# Lights.net
KiCad netlist of a schematic drawn in Altium Designer
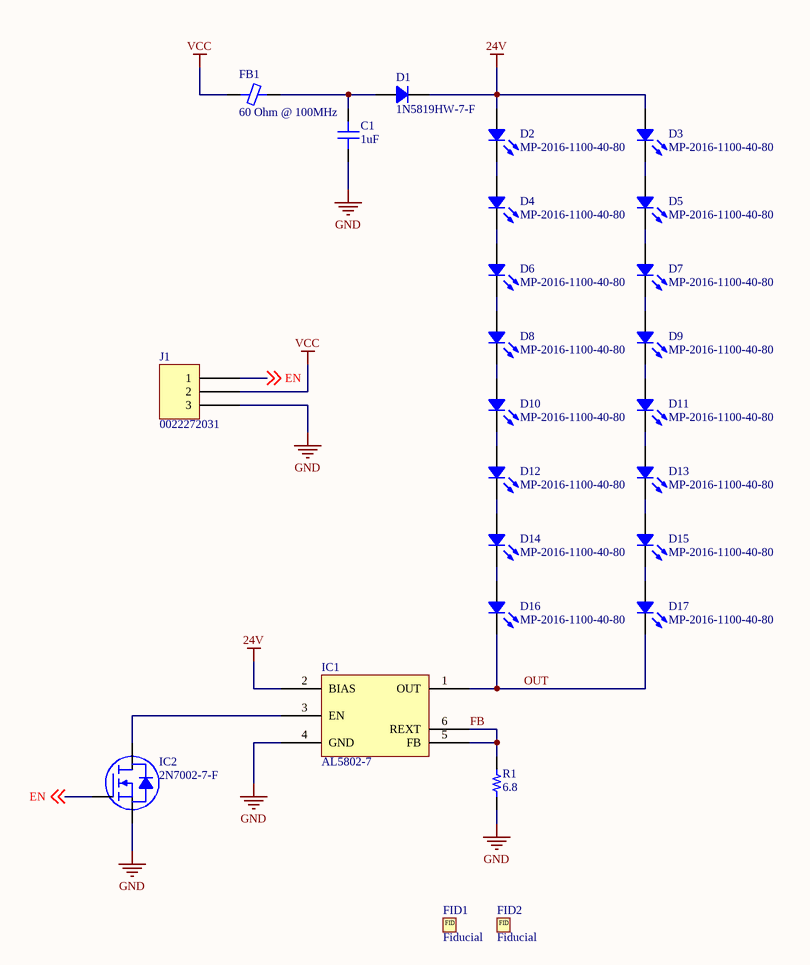
[diagram p0: Lights.SchDoc]

(export (version "E")
  (design (tool "Eeschema 10.0.6"))
  (components
    (comp (ref "C1")
      (value "1uF")
      (footprint "CAP 0603/1608")
      (description "CAP CER 1UF 50V X7R 0603")
      (fields (field (name "PART NUMBER") "UMK107AB7105KA-T") (field (name "MANUFACTURER") "Taiyo Yuden"))
      (libsource (lib "Celestial Library Database") (part "Capacitor"))
    )
    (comp (ref "D1")
      (value "1N5819HW-7-F")
      (footprint "SOD-123")
      (description "DIODE SCHOTTKY 40V 1A SOD123")
      (fields (field (name "MANUFACTURER") "Diodes Incorporated"))
      (libsource (lib "Celestial Library Database") (part "Diode"))
    )
    (comp (ref "D2")
      (value "MP-2016-1100-40-80")
      (footprint "LUMINUS MP-2016")
      (description "LED XNOVA NEUTRAL WHT 4000K 0806")
      (fields (field (name "MANUFACTURER") "Luminus Devices Inc."))
      (libsource (lib "Celestial Library Database") (part "LED"))
    )
    (comp (ref "D3")
      (value "MP-2016-1100-40-80")
      (footprint "LUMINUS MP-2016")
      (description "LED XNOVA NEUTRAL WHT 4000K 0806")
      (fields (field (name "MANUFACTURER") "Luminus Devices Inc."))
      (libsource (lib "Celestial Library Database") (part "LED"))
    )
    (comp (ref "D4")
      (value "MP-2016-1100-40-80")
      (footprint "LUMINUS MP-2016")
      (description "LED XNOVA NEUTRAL WHT 4000K 0806")
      (fields (field (name "MANUFACTURER") "Luminus Devices Inc."))
      (libsource (lib "Celestial Library Database") (part "LED"))
    )
    (comp (ref "D5")
      (value "MP-2016-1100-40-80")
      (footprint "LUMINUS MP-2016")
      (description "LED XNOVA NEUTRAL WHT 4000K 0806")
      (fields (field (name "MANUFACTURER") "Luminus Devices Inc."))
      (libsource (lib "Celestial Library Database") (part "LED"))
    )
    (comp (ref "D6")
      (value "MP-2016-1100-40-80")
      (footprint "LUMINUS MP-2016")
      (description "LED XNOVA NEUTRAL WHT 4000K 0806")
      (fields (field (name "MANUFACTURER") "Luminus Devices Inc."))
      (libsource (lib "Celestial Library Database") (part "LED"))
    )
    (comp (ref "D7")
      (value "MP-2016-1100-40-80")
      (footprint "LUMINUS MP-2016")
      (description "LED XNOVA NEUTRAL WHT 4000K 0806")
      (fields (field (name "MANUFACTURER") "Luminus Devices Inc."))
      (libsource (lib "Celestial Library Database") (part "LED"))
    )
    (comp (ref "D8")
      (value "MP-2016-1100-40-80")
      (footprint "LUMINUS MP-2016")
      (description "LED XNOVA NEUTRAL WHT 4000K 0806")
      (fields (field (name "MANUFACTURER") "Luminus Devices Inc."))
      (libsource (lib "Celestial Library Database") (part "LED"))
    )
    (comp (ref "D9")
      (value "MP-2016-1100-40-80")
      (footprint "LUMINUS MP-2016")
      (description "LED XNOVA NEUTRAL WHT 4000K 0806")
      (fields (field (name "MANUFACTURER") "Luminus Devices Inc."))
      (libsource (lib "Celestial Library Database") (part "LED"))
    )
    (comp (ref "D10")
      (value "MP-2016-1100-40-80")
      (footprint "LUMINUS MP-2016")
      (description "LED XNOVA NEUTRAL WHT 4000K 0806")
      (fields (field (name "MANUFACTURER") "Luminus Devices Inc."))
      (libsource (lib "Celestial Library Database") (part "LED"))
    )
    (comp (ref "D11")
      (value "MP-2016-1100-40-80")
      (footprint "LUMINUS MP-2016")
      (description "LED XNOVA NEUTRAL WHT 4000K 0806")
      (fields (field (name "MANUFACTURER") "Luminus Devices Inc."))
      (libsource (lib "Celestial Library Database") (part "LED"))
    )
    (comp (ref "D12")
      (value "MP-2016-1100-40-80")
      (footprint "LUMINUS MP-2016")
      (description "LED XNOVA NEUTRAL WHT 4000K 0806")
      (fields (field (name "MANUFACTURER") "Luminus Devices Inc."))
      (libsource (lib "Celestial Library Database") (part "LED"))
    )
    (comp (ref "D13")
      (value "MP-2016-1100-40-80")
      (footprint "LUMINUS MP-2016")
      (description "LED XNOVA NEUTRAL WHT 4000K 0806")
      (fields (field (name "MANUFACTURER") "Luminus Devices Inc."))
      (libsource (lib "Celestial Library Database") (part "LED"))
    )
    (comp (ref "D14")
      (value "MP-2016-1100-40-80")
      (footprint "LUMINUS MP-2016")
      (description "LED XNOVA NEUTRAL WHT 4000K 0806")
      (fields (field (name "MANUFACTURER") "Luminus Devices Inc."))
      (libsource (lib "Celestial Library Database") (part "LED"))
    )
    (comp (ref "D15")
      (value "MP-2016-1100-40-80")
      (footprint "LUMINUS MP-2016")
      (description "LED XNOVA NEUTRAL WHT 4000K 0806")
      (fields (field (name "MANUFACTURER") "Luminus Devices Inc."))
      (libsource (lib "Celestial Library Database") (part "LED"))
    )
    (comp (ref "D16")
      (value "MP-2016-1100-40-80")
      (footprint "LUMINUS MP-2016")
      (description "LED XNOVA NEUTRAL WHT 4000K 0806")
      (fields (field (name "MANUFACTURER") "Luminus Devices Inc."))
      (libsource (lib "Celestial Library Database") (part "LED"))
    )
    (comp (ref "D17")
      (value "MP-2016-1100-40-80")
      (footprint "LUMINUS MP-2016")
      (description "LED XNOVA NEUTRAL WHT 4000K 0806")
      (fields (field (name "MANUFACTURER") "Luminus Devices Inc."))
      (libsource (lib "Celestial Library Database") (part "LED"))
    )
    (comp (ref "FB1")
      (value "60 Ohm @ 100MHz")
      (footprint "FER 0603/1608")
      (description "FERRITE CHIP 60 OHM 2000MA 0603")
      (fields
        (field (name "PART NUMBER") "CIC10J600NC")
        (field (name "MANUFACTURER") "Samsung Electro-Mechanics America, Inc.")
      )
      (libsource (lib "Celestial Library Database") (part "Ferrite Chip"))
    )
    (comp (ref "FID1")
      (value "Fiducial")
      (footprint "1MM FID")
      (libsource (lib "Fiducial") (part "Fiducial"))
    )
    (comp (ref "FID2")
      (value "Fiducial")
      (footprint "1MM FID")
      (libsource (lib "Fiducial") (part "Fiducial"))
    )
    (comp (ref "IC1")
      (value "AL5802-7")
      (footprint "DIODES SOT-23-6 W6")
      (description "IC LED DRVR LIN DIM 120MA SOT26")
      (fields (field (name "MANUFACTURER") "Diodes Incorporated"))
      (libsource (lib "Celestial Library Database") (part "DIODES INC AL5802"))
    )
    (comp (ref "IC2")
      (value "2N7002-7-F")
      (footprint "DIODES SOT-23-3")
      (description "MOSFET N-CH 60V 115MA SOT23-3")
      (fields (field (name "MANUFACTURER") "Diodes Incorporated"))
      (libsource (lib "Celestial Library Database") (part "DIODES INC MOSFET N-CH SOT-23-3"))
    )
    (comp (ref "J1")
      (value "0022272031")
      (footprint "MOLEX KK 0022272031")
      (description "CONN HEADER 3POS .100 VERT TIN")
      (fields (field (name "MANUFACTURER") "Molex, LLC"))
      (libsource (lib "Celestial Library Database") (part "3 Pin"))
    )
    (comp (ref "R1")
      (value "6.8")
      (footprint "RES 0805/2012")
      (description "RES SMD 6.8 OHM 1% 1/8W 0805")
      (fields
        (field (name "PART NUMBER") "ERJ-6RQF6R8V")
        (field (name "MANUFACTURER") "Panasonic Electronic Components")
      )
      (libsource (lib "Celestial Library Database") (part "Resistor"))
    )
  )
  (nets
    (net (code "1") (name "/FB") (class "Default")
      (node (ref "IC1") (pin "5") (pinfunction "FB_5") (pintype "passive"))
      (node (ref "IC1") (pin "6") (pinfunction "REXT_6") (pintype "passive"))
      (node (ref "R1") (pin "2") (pinfunction "2_2") (pintype "passive"))
    )
    (net (code "2") (name "/OUT") (class "Default")
      (node (ref "D16") (pin "2") (pinfunction "2_2") (pintype "passive"))
      (node (ref "D17") (pin "2") (pinfunction "2_2") (pintype "passive"))
      (node (ref "IC1") (pin "1") (pinfunction "OUT_1") (pintype "passive"))
    )
    (net (code "3") (name "24V") (class "Default")
      (node (ref "D1") (pin "2") (pinfunction "2_2") (pintype "passive"))
      (node (ref "D2") (pin "1") (pinfunction "1_1") (pintype "passive"))
      (node (ref "D3") (pin "1") (pinfunction "1_1") (pintype "passive"))
      (node (ref "IC1") (pin "2") (pinfunction "BIAS_2") (pintype "passive"))
    )
    (net (code "4") (name "EN") (class "Default")
      (node (ref "IC2") (pin "1") (pinfunction "G_1") (pintype "passive"))
      (node (ref "J1") (pin "1") (pinfunction "1_1") (pintype "passive"))
    )
    (net (code "5") (name "GND") (class "Default")
      (node (ref "C1") (pin "1") (pinfunction "1_1") (pintype "passive"))
      (node (ref "IC1") (pin "4") (pinfunction "GND_4") (pintype "passive"))
      (node (ref "IC2") (pin "3") (pinfunction "S_3") (pintype "passive"))
      (node (ref "J1") (pin "3") (pinfunction "3_3") (pintype "passive"))
      (node (ref "R1") (pin "1") (pinfunction "1_1") (pintype "passive"))
    )
    (net (code "6") (name "Net-(C1-Pad2)") (class "Default")
      (node (ref "C1") (pin "2") (pinfunction "2_2") (pintype "passive"))
      (node (ref "D1") (pin "1") (pinfunction "1_1") (pintype "passive"))
      (node (ref "FB1") (pin "2") (pinfunction "2_2") (pintype "passive"))
    )
    (net (code "7") (name "Net-(D2-Pad2)") (class "Default")
      (node (ref "D2") (pin "2") (pinfunction "2_2") (pintype "passive"))
      (node (ref "D4") (pin "1") (pinfunction "1_1") (pintype "passive"))
    )
    (net (code "8") (name "Net-(D3-Pad2)") (class "Default")
      (node (ref "D3") (pin "2") (pinfunction "2_2") (pintype "passive"))
      (node (ref "D5") (pin "1") (pinfunction "1_1") (pintype "passive"))
    )
    (net (code "9") (name "Net-(D4-Pad2)") (class "Default")
      (node (ref "D4") (pin "2") (pinfunction "2_2") (pintype "passive"))
      (node (ref "D6") (pin "1") (pinfunction "1_1") (pintype "passive"))
    )
    (net (code "10") (name "Net-(D5-Pad2)") (class "Default")
      (node (ref "D5") (pin "2") (pinfunction "2_2") (pintype "passive"))
      (node (ref "D7") (pin "1") (pinfunction "1_1") (pintype "passive"))
    )
    (net (code "11") (name "Net-(D6-Pad2)") (class "Default")
      (node (ref "D6") (pin "2") (pinfunction "2_2") (pintype "passive"))
      (node (ref "D8") (pin "1") (pinfunction "1_1") (pintype "passive"))
    )
    (net (code "12") (name "Net-(D7-Pad2)") (class "Default")
      (node (ref "D7") (pin "2") (pinfunction "2_2") (pintype "passive"))
      (node (ref "D9") (pin "1") (pinfunction "1_1") (pintype "passive"))
    )
    (net (code "13") (name "Net-(D10-Pad1)") (class "Default")
      (node (ref "D10") (pin "1") (pinfunction "1_1") (pintype "passive"))
      (node (ref "D8") (pin "2") (pinfunction "2_2") (pintype "passive"))
    )
    (net (code "14") (name "Net-(D10-Pad2)") (class "Default")
      (node (ref "D10") (pin "2") (pinfunction "2_2") (pintype "passive"))
      (node (ref "D12") (pin "1") (pinfunction "1_1") (pintype "passive"))
    )
    (net (code "15") (name "Net-(D11-Pad1)") (class "Default")
      (node (ref "D11") (pin "1") (pinfunction "1_1") (pintype "passive"))
      (node (ref "D9") (pin "2") (pinfunction "2_2") (pintype "passive"))
    )
    (net (code "16") (name "Net-(D11-Pad2)") (class "Default")
      (node (ref "D11") (pin "2") (pinfunction "2_2") (pintype "passive"))
      (node (ref "D13") (pin "1") (pinfunction "1_1") (pintype "passive"))
    )
    (net (code "17") (name "Net-(D12-Pad2)") (class "Default")
      (node (ref "D12") (pin "2") (pinfunction "2_2") (pintype "passive"))
      (node (ref "D14") (pin "1") (pinfunction "1_1") (pintype "passive"))
    )
    (net (code "18") (name "Net-(D13-Pad2)") (class "Default")
      (node (ref "D13") (pin "2") (pinfunction "2_2") (pintype "passive"))
      (node (ref "D15") (pin "1") (pinfunction "1_1") (pintype "passive"))
    )
    (net (code "19") (name "Net-(D14-Pad2)") (class "Default")
      (node (ref "D14") (pin "2") (pinfunction "2_2") (pintype "passive"))
      (node (ref "D16") (pin "1") (pinfunction "1_1") (pintype "passive"))
    )
    (net (code "20") (name "Net-(D15-Pad2)") (class "Default")
      (node (ref "D15") (pin "2") (pinfunction "2_2") (pintype "passive"))
      (node (ref "D17") (pin "1") (pinfunction "1_1") (pintype "passive"))
    )
    (net (code "21") (name "Net-(IC1-EN)") (class "Default")
      (node (ref "IC1") (pin "3") (pinfunction "EN_3") (pintype "passive"))
      (node (ref "IC2") (pin "2") (pinfunction "D_2") (pintype "passive"))
    )
    (net (code "22") (name "VCC") (class "Default")
      (node (ref "FB1") (pin "1") (pinfunction "1_1") (pintype "passive"))
      (node (ref "J1") (pin "2") (pinfunction "2_2") (pintype "passive"))
    )
  )
)
